# Fan_Driver.net
KiCad netlist of a schematic drawn in Altium Designer
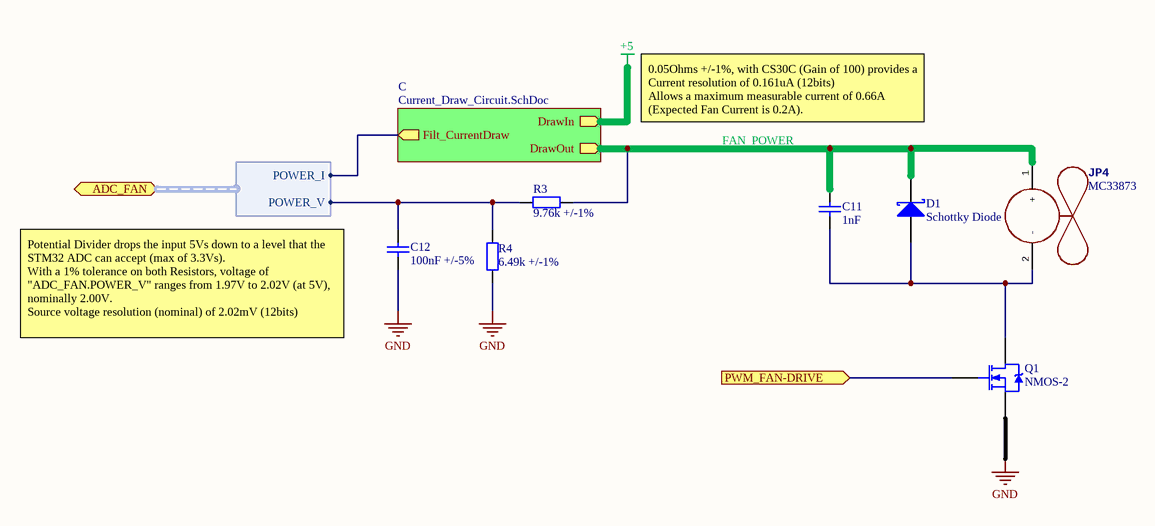
[diagram p0: Fan_Driver.SchDoc]

(export (version "E")
  (design (tool "Eeschema 10.0.6"))
  (components
    (comp (ref "C11")
      (value "1nF")
      (footprint "CAPC1608X06N (0603)")
      (description "Capacitor (Semiconductor SIM Model)")
      (fields (field (name "Comment") "Cap Semi") (field (name "PUBLISHER") "Altium Limited"))
      (libsource (lib "miStepper_SchematicLib") (part "Cap Semi"))
    )
    (comp (ref "C12")
      (value "100nF +/-5%")
      (footprint "CAPC1608X06N (0603)")
      (description "Capacitor (Semiconductor SIM Model)")
      (fields (field (name "Comment") "Cap Semi") (field (name "PUBLISHER") "Altium Limited"))
      (libsource (lib "miStepper_SchematicLib") (part "Cap Semi"))
    )
    (comp (ref "D1")
      (value "Schottky Diode")
      (footprint "SODFL350X115-2N")
      (description "Schottky Rectifier")
      (fields (field (name "PUBLISHER") "Altium Limited"))
      (libsource (lib "miStepper_SchematicLib") (part "Diode"))
    )
    (comp (ref "JP4")
      (value "MC33873")
      (footprint "JP1Y")
      (description "Motor")
      (libsource (lib "miStepper_SchematicLib") (part "MC33873"))
    )
    (comp (ref "Q1")
      (value "NMOS-2")
      (footprint "SOT230P700X180-4N")
      (description "N-Channel Power MOSFET")
      (fields (field (name "PUBLISHER") "Altium Limited"))
      (libsource (lib "miStepper_SchematicLib") (part "NMOS-2"))
    )
    (comp (ref "R3")
      (value "9.76k +/-1%")
      (footprint "RESC1608X06N (0603)")
      (description "Resistor")
      (fields (field (name "Comment") "Res") (field (name "PUBLISHER") "Altium Limited"))
      (libsource (lib "") (part "Res_1"))
    )
    (comp (ref "R4")
      (value "6.49k +/-1%")
      (footprint "RESC1608X06N (0603)")
      (description "Resistor")
      (fields (field (name "Comment") "Res") (field (name "PUBLISHER") "Altium Limited"))
      (libsource (lib "miStepper_SchematicLib") (part "Res"))
    )
  )
  (nets
    (net (code "3") (name "/FAN_POWER") (class "Default")
      (node (ref "C11") (pin "2") (pinfunction "2_2") (pintype "passive"))
      (node (ref "D1") (pin "1") (pinfunction "K_1") (pintype "passive"))
      (node (ref "JP4") (pin "1") (pinfunction "+_1") (pintype "passive"))
      (node (ref "R3") (pin "2") (pinfunction "2_2") (pintype "passive"))
    )
    (net (code "5") (name "/PWM_FAN-DRIVE") (class "Default")
      (node (ref "Q1") (pin "1") (pinfunction "G_1") (pintype "passive"))
    )
    (net (code "7") (name "GND") (class "Default")
      (node (ref "C12") (pin "1") (pinfunction "1_1") (pintype "passive"))
      (node (ref "Q1") (pin "3") (pinfunction "S_3") (pintype "passive"))
      (node (ref "R4") (pin "1") (pinfunction "1_1") (pintype "passive"))
    )
    (net (code "8") (name "Net-(C12-Pad2)") (class "Default")
      (node (ref "C12") (pin "2") (pinfunction "2_2") (pintype "passive"))
      (node (ref "R3") (pin "1") (pinfunction "1_1") (pintype "passive"))
      (node (ref "R4") (pin "2") (pinfunction "2_2") (pintype "passive"))
    )
    (net (code "9") (name "Net-(D1-A)") (class "Default")
      (node (ref "C11") (pin "1") (pinfunction "1_1") (pintype "passive"))
      (node (ref "D1") (pin "2") (pinfunction "A_2") (pintype "passive"))
      (node (ref "JP4") (pin "2") (pinfunction "-_2") (pintype "passive"))
      (node (ref "Q1") (pin "2") (pinfunction "D_2") (pintype "passive"))
    )
  )
)
